# BELL.net
KiCad netlist of a schematic drawn in Altium Designer
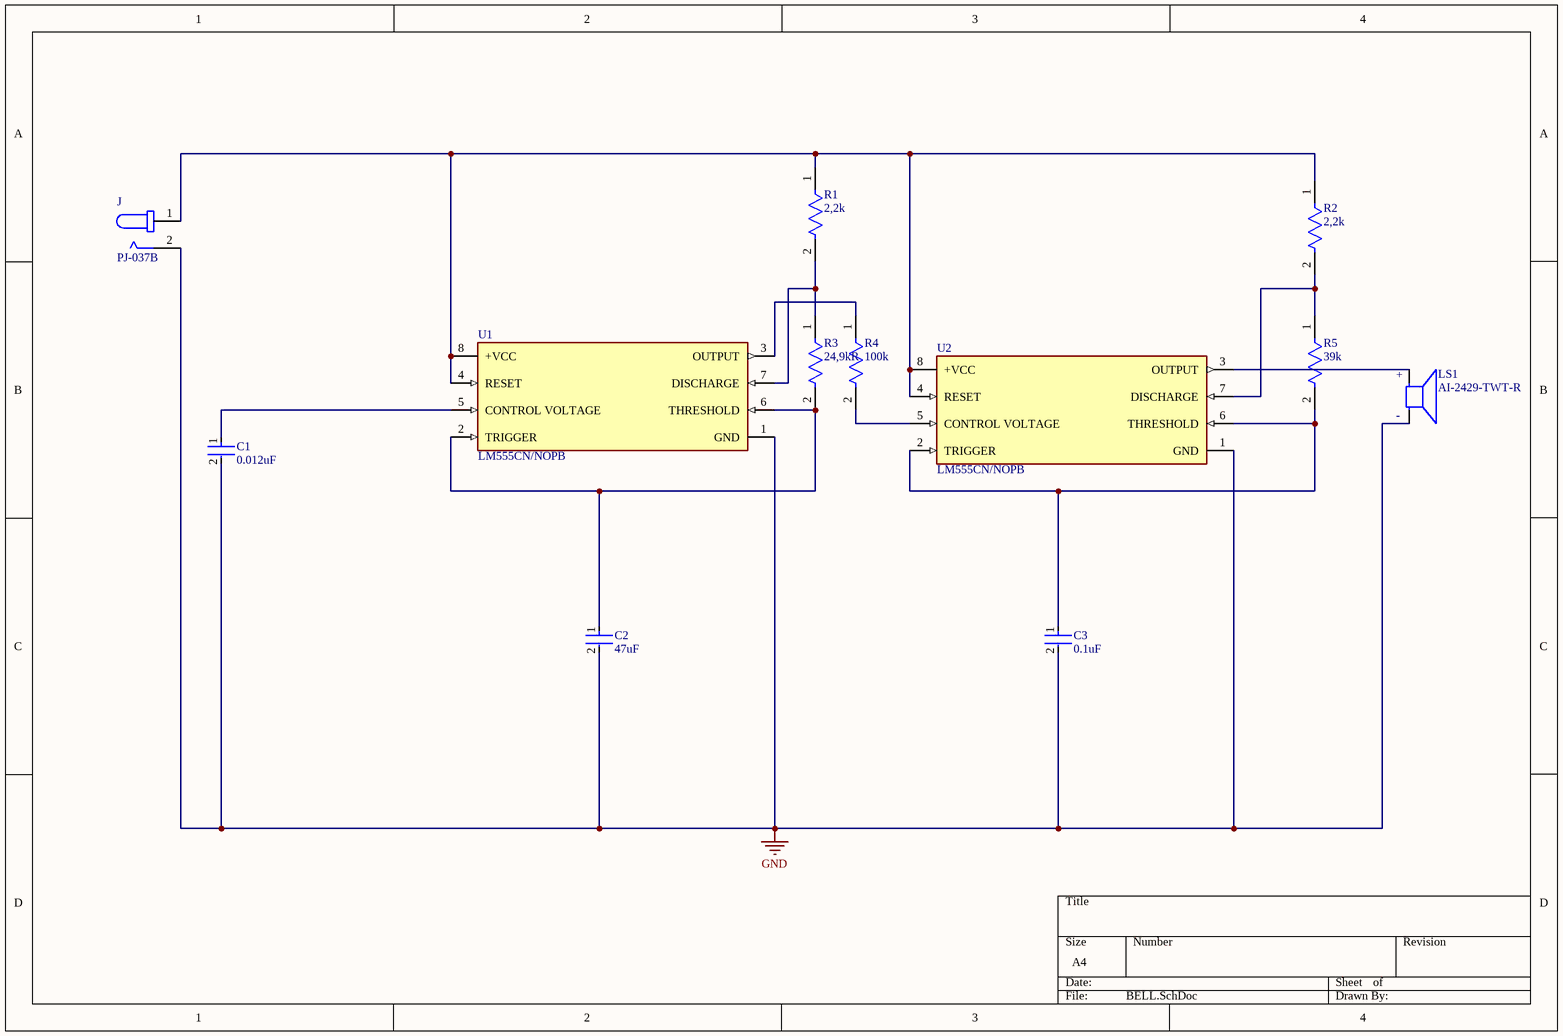
[diagram p0: BELL.SchDoc]

(export (version "E")
  (design (tool "Eeschema 10.0.6"))
  (components
    (comp (ref "C1")
      (value "0.012uF")
      (footprint "FP-GRM033-0_03-IPC_B")
      (description "Cap Ceramic 0.012uF 6.3V X6S 10% SMD 0201 105°C Paper T/R")
      (fields (field (name "TOLERANCE") "10%") (field (name "MANUFACTURER") "Murata"))
      (libsource (lib "BELL_Schlib") (part "CMP-2010-01245-2"))
    )
    (comp (ref "C2")
      (value "47uF")
      (footprint "FP-MK325M-IPC_B")
      (description "1210 47 uF 10 V ±20% Tolerance X7R Multilayer Ceramic Capacitor")
      (fields (field (name "TOLERANCE") "20%") (field (name "VOLTAGE") "10V"))
      (libsource (lib "BELL_Schlib") (part "CMP-2000-06559-2"))
    )
    (comp (ref "C3")
      (value "0.1uF")
      (footprint "FP-CL46-IPC_B")
      (description "Ceramic capacitor SMD-0402 100nF /10V X5R# K +-10%, Samsung, RoHS")
      (fields (field (name "TOLERANCE") "10%") (field (name "MANUFACTURER") "Samsung"))
      (libsource (lib "BELL_Schlib") (part "CMP-13271-002143-1"))
    )
    (comp (ref "J")
      (value "PJ-037B")
      (footprint "CUI_PJ-037B")
      (description "2.5 x 6.5 mm, 2.5 A, Horizontal, Through Hole, Dc Power Jack Connector")
      (fields (field (name "MF") "CUI Devices") (field (name "MANUFACTURER") "CUI"))
      (libsource (lib "BELL_Schlib") (part "PJ-037B"))
    )
    (comp (ref "LS1")
      (value "AI-2429-TWT-R")
      (footprint "XDCR_AI-2429-TWT-R")
      (description "Audio Indicator Piezo 12VDC 10mA Pin 3VDC 2400Hz to 3400Hz Through Hole")
      (fields (field (name "MF") "PUI Audio") (field (name "MANUFACTURER") "Projects Unlimited"))
      (libsource (lib "BELL_Schlib") (part "AI-2429-TWT-R"))
    )
    (comp (ref "R1")
      (value "2,2k")
      (footprint "FP-RMCF0805-IPC_B")
      (description "Res Thick Film 0805 2.2K Ohm 1% 0.125W ±100ppm/°C Molded SMD Paper T/R")
      (fields (field (name "TOLERANCE") "1%") (field (name "MANUFACTURER") "Stackpole Electronics"))
      (libsource (lib "BELL_Schlib") (part "CMP-26527-000414-1"))
    )
    (comp (ref "R2")
      (value "2,2k")
      (footprint "FP-RMCF0805-IPC_B")
      (description "Res Thick Film 0805 2.2K Ohm 1% 0.125W ±100ppm/°C Molded SMD Paper T/R")
      (fields (field (name "TOLERANCE") "1%") (field (name "MANUFACTURER") "Stackpole Electronics"))
      (libsource (lib "BELL_Schlib") (part "CMP-26527-000414-1"))
    )
    (comp (ref "R3")
      (value "24,9kR")
      (footprint "FP-RT0805-IPC_B")
      (description "Res Thin Film 0805 24.9K Ohm 0.1% 1/8W ±25ppm/°C Molded SMD SMD Paper T/R")
      (fields (field (name "TOLERANCE") "0.0025") (field (name "MANUFACTURER") "Yageo"))
      (libsource (lib "BELL_Schlib") (part "CMP-03412-011084-1"))
    )
    (comp (ref "R4")
      (value "100k")
      (footprint "FP-CRCW0805-e3-IPC_B")
      (description "Res Thick Film 0805 100K Ohm 1% 0.125W ±100ppm/°C Molded SMD Paper T/R")
      (fields (field (name "TOLERANCE") "1%") (field (name "MANUFACTURER") "Stackpole Electronics"))
      (libsource (lib "BELL_Schlib") (part "CMP-2001-04187-2"))
    )
    (comp (ref "R5")
      (value "39k")
      (footprint "FP-KTR10-IPC_B")
      (description "Res High Voltage 0805 39K Ohm 1/8W 1% SMD")
      (fields (field (name "TOLERANCE") "1%") (field (name "MANUFACTURER") "Rohm"))
      (libsource (lib "BELL_Schlib") (part "CMP-08839-006009-1"))
    )
    (comp (ref "U1")
      (value "LM555CN/NOPB")
      (footprint "FP-P0008A-MFG")
      (description "Timer; 8-PIN Mdip; 8 Pins; +18 V (max.); 3 ma (typ.) @ 5 V, +25 C Supply")
      (fields
        (field (name "MANUFACTURER") "Texas Instruments")
        (field (name "OCTOPART") "https://octopart.com/lm555cn%2Fnopb-texas+instruments-24814897")
      )
      (libsource (lib "BELL_Schlib") (part "CMP-0056-00016-4"))
    )
    (comp (ref "U2")
      (value "LM555CN/NOPB")
      (footprint "FP-P0008A-MFG")
      (description "Timer; 8-PIN Mdip; 8 Pins; +18 V (max.); 3 ma (typ.) @ 5 V, +25 C Supply")
      (fields
        (field (name "MANUFACTURER") "Texas Instruments")
        (field (name "OCTOPART") "https://octopart.com/lm555cn%2Fnopb-texas+instruments-24814897")
      )
      (libsource (lib "BELL_Schlib") (part "CMP-0056-00016-4"))
    )
  )
  (nets
    (net (code "1") (name "GND") (class "Default")
      (node (ref "C1") (pin "2") (pinfunction "2_2") (pintype "passive"))
      (node (ref "C2") (pin "2") (pinfunction "2_2") (pintype "passive"))
      (node (ref "C3") (pin "2") (pinfunction "2_2") (pintype "passive"))
      (node (ref "J") (pin "2") (pinfunction "2_2") (pintype "passive"))
      (node (ref "LS1") (pin "N") (pinfunction "N_N") (pintype "passive"))
      (node (ref "U1") (pin "1") (pinfunction "GND_1") (pintype "power_in"))
      (node (ref "U2") (pin "1") (pinfunction "GND_1") (pintype "power_in"))
    )
    (net (code "2") (name "Net-(U1-+VCC)") (class "Default")
      (node (ref "J") (pin "1") (pinfunction "1_1") (pintype "passive"))
      (node (ref "R1") (pin "1") (pinfunction "1_1") (pintype "passive"))
      (node (ref "R2") (pin "1") (pinfunction "1_1") (pintype "passive"))
      (node (ref "U1") (pin "4") (pinfunction "RESET_4") (pintype "input"))
      (node (ref "U1") (pin "8") (pinfunction "+VCC_8") (pintype "power_in"))
      (node (ref "U2") (pin "4") (pinfunction "RESET_4") (pintype "input"))
      (node (ref "U2") (pin "8") (pinfunction "+VCC_8") (pintype "power_in"))
    )
    (net (code "3") (name "Net-(U1-CONTROL_VOLTAGE)") (class "Default")
      (node (ref "C1") (pin "1") (pinfunction "1_1") (pintype "passive"))
      (node (ref "U1") (pin "5") (pinfunction "CONTROL_VOLTAGE_5") (pintype "input"))
    )
    (net (code "4") (name "Net-(U1-DISCHARGE)") (class "Default")
      (node (ref "R1") (pin "2") (pinfunction "2_2") (pintype "passive"))
      (node (ref "R3") (pin "1") (pinfunction "1_1") (pintype "passive"))
      (node (ref "U1") (pin "7") (pinfunction "DISCHARGE_7") (pintype "input"))
    )
    (net (code "5") (name "Net-(U1-OUTPUT)") (class "Default")
      (node (ref "R4") (pin "1") (pinfunction "1_1") (pintype "passive"))
      (node (ref "U1") (pin "3") (pinfunction "OUTPUT_3") (pintype "output"))
    )
    (net (code "6") (name "Net-(U1-THRESHOLD)") (class "Default")
      (node (ref "C2") (pin "1") (pinfunction "1_1") (pintype "passive"))
      (node (ref "R3") (pin "2") (pinfunction "2_2") (pintype "passive"))
      (node (ref "U1") (pin "2") (pinfunction "TRIGGER_2") (pintype "input"))
      (node (ref "U1") (pin "6") (pinfunction "THRESHOLD_6") (pintype "input"))
    )
    (net (code "7") (name "Net-(U2-CONTROL_VOLTAGE)") (class "Default")
      (node (ref "R4") (pin "2") (pinfunction "2_2") (pintype "passive"))
      (node (ref "U2") (pin "5") (pinfunction "CONTROL_VOLTAGE_5") (pintype "input"))
    )
    (net (code "8") (name "Net-(U2-DISCHARGE)") (class "Default")
      (node (ref "R2") (pin "2") (pinfunction "2_2") (pintype "passive"))
      (node (ref "R5") (pin "1") (pinfunction "1_1") (pintype "passive"))
      (node (ref "U2") (pin "7") (pinfunction "DISCHARGE_7") (pintype "input"))
    )
    (net (code "9") (name "Net-(U2-OUTPUT)") (class "Default")
      (node (ref "LS1") (pin "P") (pinfunction "P_P") (pintype "passive"))
      (node (ref "U2") (pin "3") (pinfunction "OUTPUT_3") (pintype "output"))
    )
    (net (code "10") (name "Net-(U2-THRESHOLD)") (class "Default")
      (node (ref "C3") (pin "1") (pinfunction "1_1") (pintype "passive"))
      (node (ref "R5") (pin "2") (pinfunction "2_2") (pintype "passive"))
      (node (ref "U2") (pin "2") (pinfunction "TRIGGER_2") (pintype "input"))
      (node (ref "U2") (pin "6") (pinfunction "THRESHOLD_6") (pintype "input"))
    )
  )
)
